# Power_Supply.net
KiCad netlist of a schematic drawn in Altium Designer
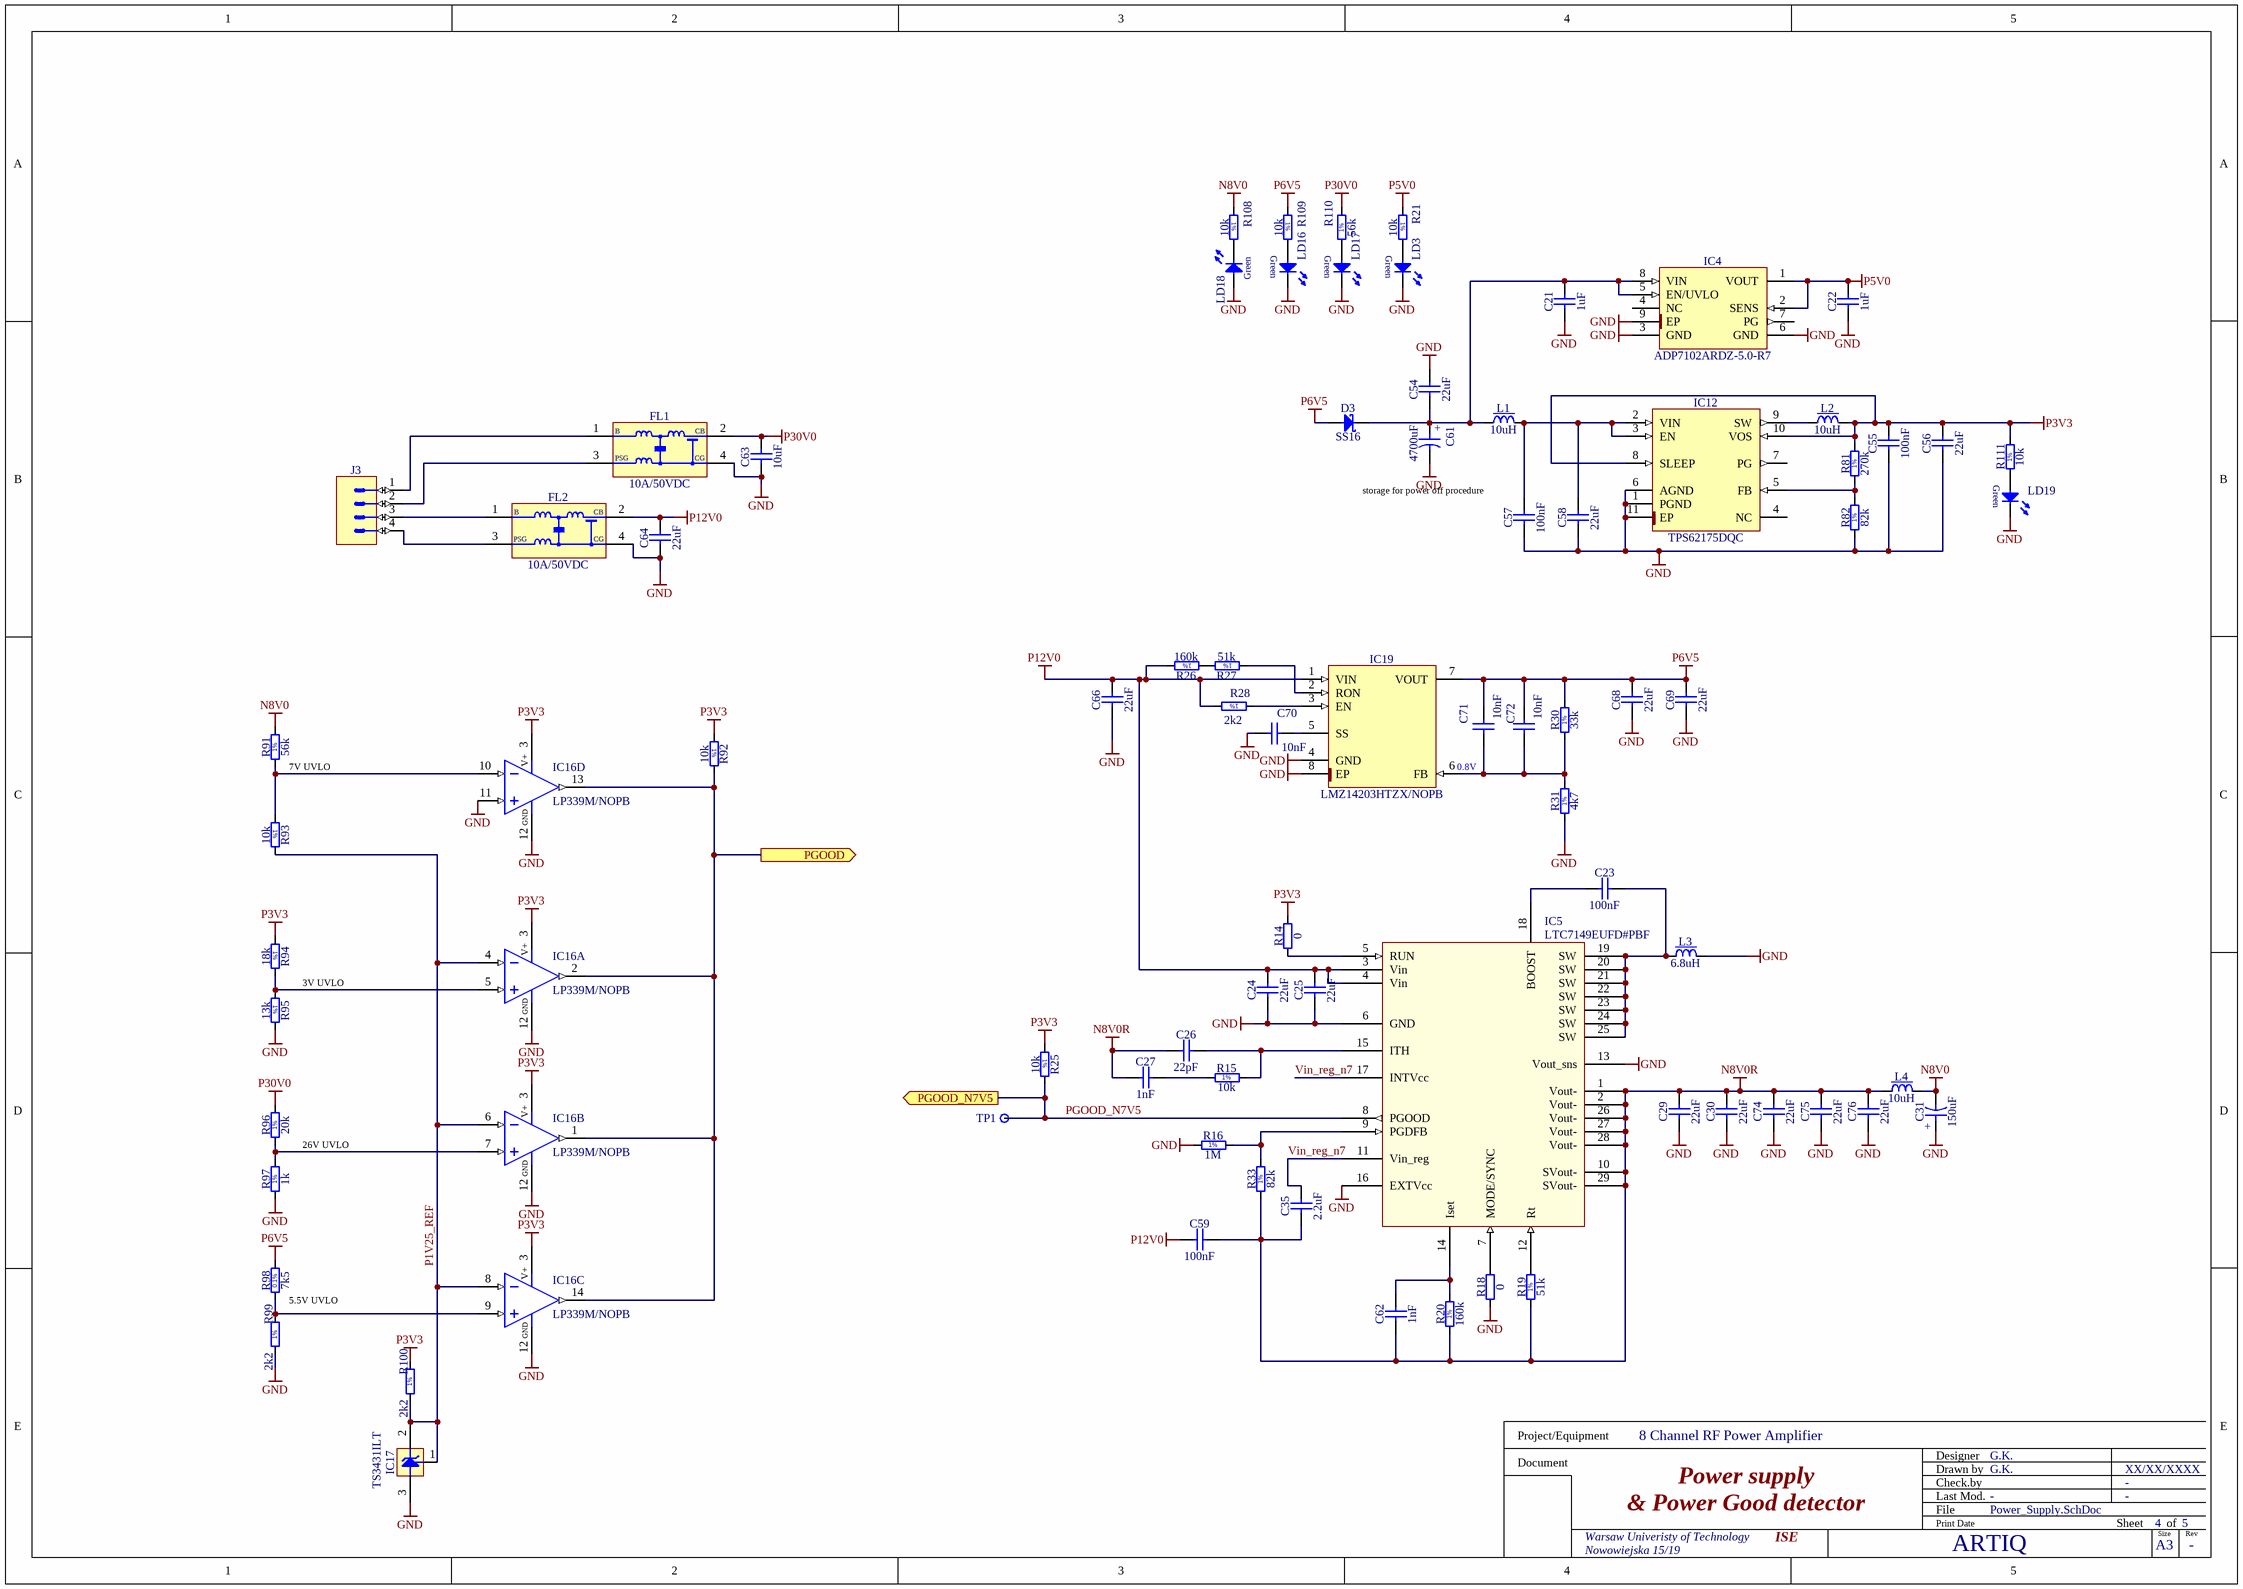
[diagram p0: Power_Supply.SchDoc]

(export (version "E")
  (design (tool "Eeschema 10.0.6"))
  (components
    (comp (ref "C21")
      (value "1uF")
      (footprint "CAPC2012X140N")
      (description "Non-polarised capacitor")
      (fields
        (field (name "PART NUMBER") "CC0805_1UF_35V_20%_X7R")
        (field (name "VOLTAGE") "35V")
        (field (name "AUTHOR") "CERN DEM JLC")
      )
      (libsource (lib "Capacitors") (part "Capacitor - non polarized"))
    )
    (comp (ref "C22")
      (value "1uF")
      (footprint "CAPC2012X140N")
      (description "Non-polarised capacitor")
      (fields
        (field (name "PART NUMBER") "CC0805_1UF_35V_20%_X7R")
        (field (name "VOLTAGE") "35V")
        (field (name "AUTHOR") "CERN DEM JLC")
      )
      (libsource (lib "Capacitors") (part "Capacitor - non polarized"))
    )
    (comp (ref "C23")
      (value "100nF")
      (footprint "CAPC1005X55N")
      (description "Non-polarised capacitor")
      (fields
        (field (name "PART NUMBER") "CC0402_100NF_16V_10%_X7R")
        (field (name "VOLTAGE") "16V")
        (field (name "AUTHOR") "CERN DEM JLC")
      )
      (libsource (lib "Capacitors") (part "Capacitor - non polarized"))
    )
    (comp (ref "C24")
      (value "22uF")
      (footprint "CAPC2012X135N")
      (description "Non-polarised capacitor")
      (fields
        (field (name "PART NUMBER") "CC0805_22UF_16V_10%_X5R")
        (field (name "VOLTAGE") "16V")
        (field (name "AUTHOR") "CERN DEM JLC")
      )
      (libsource (lib "Capacitors") (part "Capacitor - non polarized"))
    )
    (comp (ref "C25")
      (value "22uF")
      (footprint "CAPC2012X135N")
      (description "Non-polarised capacitor")
      (fields
        (field (name "PART NUMBER") "CC0805_22UF_16V_10%_X5R")
        (field (name "VOLTAGE") "16V")
        (field (name "AUTHOR") "CERN DEM JLC")
      )
      (libsource (lib "Capacitors") (part "Capacitor - non polarized"))
    )
    (comp (ref "C26")
      (value "22pF")
      (footprint "CAPC1005X55N")
      (description "Non-polarised capacitor")
      (fields
        (field (name "PART NUMBER") "CC0402_22PF_50V_5%_C0G")
        (field (name "VOLTAGE") "50V")
        (field (name "AUTHOR") "CERN DEM JLC")
      )
      (libsource (lib "Capacitors") (part "Capacitor - non polarized"))
    )
    (comp (ref "C27")
      (value "1nF")
      (footprint "CAPC1005X55N")
      (description "Non-polarised capacitor")
      (fields
        (field (name "PART NUMBER") "CC0402_1NF_50V_10%_X7R")
        (field (name "VOLTAGE") "50V")
        (field (name "AUTHOR") "CERN DEM JLC")
      )
      (libsource (lib "Capacitors") (part "Capacitor - non polarized"))
    )
    (comp (ref "C29")
      (value "22uF")
      (footprint "CAPC2012X135N")
      (description "Non-polarised capacitor")
      (fields
        (field (name "PART NUMBER") "CC0805_22UF_16V_10%_X5R")
        (field (name "VOLTAGE") "16V")
        (field (name "AUTHOR") "CERN DEM JLC")
      )
      (libsource (lib "Capacitors") (part "Capacitor - non polarized"))
    )
    (comp (ref "C30")
      (value "22uF")
      (footprint "CAPC2012X135N")
      (description "Non-polarised capacitor")
      (fields
        (field (name "PART NUMBER") "CC0805_22UF_16V_10%_X5R")
        (field (name "VOLTAGE") "16V")
        (field (name "AUTHOR") "CERN DEM JLC")
      )
      (libsource (lib "Capacitors") (part "Capacitor - non polarized"))
    )
    (comp (ref "C31")
      (value "150uF")
      (footprint "CAPMP7343X310N")
      (description "Polarised capacitor")
      (fields
        (field (name "PART NUMBER") "CTE7343-31_150UF_16V_10%_LESR0100")
        (field (name "VOLTAGE") "16V")
        (field (name "AUTHOR") "CERN DEM JLC")
      )
      (libsource (lib "Capacitors") (part "Capacitor - polarized"))
    )
    (comp (ref "C35")
      (value "2.2uF")
      (footprint "CAPC1608X87N")
      (description "Non-polarised capacitor")
      (fields
        (field (name "PART NUMBER") "CC0603_2.2UF_16V_10%_X5R")
        (field (name "VOLTAGE") "16V")
        (field (name "AUTHOR") "CERN DEM JLC")
      )
      (libsource (lib "Capacitors") (part "Capacitor - non polarized"))
    )
    (comp (ref "C54")
      (value "22uF")
      (footprint "CAPC2012X135N")
      (description "Non-polarised capacitor")
      (fields
        (field (name "PART NUMBER") "CC0805_22UF_16V_10%_X5R")
        (field (name "VOLTAGE") "16V")
        (field (name "AUTHOR") "CERN DEM JLC")
      )
      (libsource (lib "Capacitors") (part "Capacitor - non polarized"))
    )
    (comp (ref "C55")
      (value "100nF")
      (footprint "CAPC1005X55N")
      (description "Non-polarised capacitor")
      (fields
        (field (name "PART NUMBER") "CC0402_100NF_16V_10%_X5R")
        (field (name "VOLTAGE") "16V")
        (field (name "AUTHOR") "CERN DEM JLC")
      )
      (libsource (lib "Capacitors") (part "Capacitor - non polarized"))
    )
    (comp (ref "C56")
      (value "22uF")
      (footprint "CAPC2012X135N")
      (description "Non-polarised capacitor")
      (fields
        (field (name "PART NUMBER") "CC0805_22UF_16V_10%_X5R")
        (field (name "VOLTAGE") "16V")
        (field (name "AUTHOR") "CERN DEM JLC")
      )
      (libsource (lib "Capacitors") (part "Capacitor - non polarized"))
    )
    (comp (ref "C57")
      (value "100nF")
      (footprint "CAPC1005X55N")
      (description "Non-polarised capacitor")
      (fields
        (field (name "PART NUMBER") "CC0402_100NF_16V_10%_X5R")
        (field (name "VOLTAGE") "16V")
        (field (name "AUTHOR") "CERN DEM JLC")
      )
      (libsource (lib "Capacitors") (part "Capacitor - non polarized"))
    )
    (comp (ref "C58")
      (value "22uF")
      (footprint "CAPC2012X135N")
      (description "Non-polarised capacitor")
      (fields
        (field (name "PART NUMBER") "CC0805_22UF_16V_10%_X5R")
        (field (name "VOLTAGE") "16V")
        (field (name "AUTHOR") "CERN DEM JLC")
      )
      (libsource (lib "Capacitors") (part "Capacitor - non polarized"))
    )
    (comp (ref "C59")
      (value "100nF")
      (footprint "CAPC1608X87N")
      (description "Non-polarised capacitor")
      (fields
        (field (name "PART NUMBER") "CC0603_100NF_50V_10%_X5R")
        (field (name "VOLTAGE") "50V")
        (field (name "AUTHOR") "CERN DEM MR")
      )
      (libsource (lib "Capacitors") (part "Capacitor - non polarized"))
    )
    (comp (ref "C61")
      (value "4700uF")
      (footprint "CAPAE1900X1680N")
      (description "Polarised capacitor")
      (fields
        (field (name "PART NUMBER") "CAE1900-1680_4700UF_16V_20%")
        (field (name "VOLTAGE") "16V")
        (field (name "AUTHOR") "CERN DEM JLC")
      )
      (libsource (lib "Capacitors") (part "Capacitor - polarized"))
    )
    (comp (ref "C62")
      (value "1nF")
      (footprint "CAPC1005X55N")
      (description "Non-polarised capacitor")
      (fields
        (field (name "PART NUMBER") "CC0402_1NF_50V_10%_X7R")
        (field (name "VOLTAGE") "50V")
        (field (name "AUTHOR") "CERN DEM JLC")
      )
      (libsource (lib "Capacitors") (part "Capacitor - non polarized"))
    )
    (comp (ref "C63")
      (value "10uF")
      (footprint "CAPC3216X190N")
      (description "Non-polarised capacitor")
      (fields
        (field (name "PART NUMBER") "CC1206_10UF_50V_10%_X5R_TDK_CGA5L3X5R1H106K160AB")
        (field (name "VOLTAGE") "50V")
        (field (name "AUTHOR") "CERN DEM BC")
      )
      (libsource (lib "Capacitors") (part "Capacitor - non polarized"))
    )
    (comp (ref "C64")
      (value "22uF")
      (footprint "CAPC2012X135N")
      (description "Non-polarised capacitor")
      (fields
        (field (name "PART NUMBER") "CC0805_22UF_16V_10%_X5R")
        (field (name "VOLTAGE") "16V")
        (field (name "AUTHOR") "CERN DEM JLC")
      )
      (libsource (lib "Capacitors") (part "Capacitor - non polarized"))
    )
    (comp (ref "C66")
      (value "22uF")
      (footprint "CAPC2012X135N")
      (description "Non-polarised capacitor")
      (fields
        (field (name "PART NUMBER") "CC0805_22UF_16V_10%_X5R")
        (field (name "VOLTAGE") "16V")
        (field (name "AUTHOR") "CERN DEM JLC")
      )
      (libsource (lib "Capacitors") (part "Capacitor - non polarized"))
    )
    (comp (ref "C68")
      (value "22uF")
      (footprint "CAPC2012X135N")
      (description "Non-polarised capacitor")
      (fields
        (field (name "PART NUMBER") "CC0805_22UF_16V_10%_X5R")
        (field (name "VOLTAGE") "16V")
        (field (name "AUTHOR") "CERN DEM JLC")
      )
      (libsource (lib "Capacitors") (part "Capacitor - non polarized"))
    )
    (comp (ref "C69")
      (value "22uF")
      (footprint "CAPC2012X135N")
      (description "Non-polarised capacitor")
      (fields
        (field (name "PART NUMBER") "CC0805_22UF_16V_10%_X5R")
        (field (name "VOLTAGE") "16V")
        (field (name "AUTHOR") "CERN DEM JLC")
      )
      (libsource (lib "Capacitors") (part "Capacitor - non polarized"))
    )
    (comp (ref "C70")
      (value "10nF")
      (footprint "CAPC1608X87N")
      (description "Non-polarised capacitor")
      (fields
        (field (name "PART NUMBER") "CC0603_10NF_50V_5%_C0G")
        (field (name "VOLTAGE") "50V")
        (field (name "AUTHOR") "CERN DEM JLC")
      )
      (libsource (lib "Capacitors") (part "Capacitor - non polarized"))
    )
    (comp (ref "C71")
      (value "10nF")
      (footprint "CAPC1608X87N")
      (description "Non-polarised capacitor")
      (fields
        (field (name "PART NUMBER") "CC0603_10NF_50V_5%_C0G")
        (field (name "VOLTAGE") "50V")
        (field (name "AUTHOR") "CERN DEM JLC")
      )
      (libsource (lib "Capacitors") (part "Capacitor - non polarized"))
    )
    (comp (ref "C72")
      (value "10nF")
      (footprint "CAPC1608X87N")
      (description "Non-polarised capacitor")
      (fields
        (field (name "PART NUMBER") "CC0603_10NF_50V_5%_C0G")
        (field (name "VOLTAGE") "50V")
        (field (name "AUTHOR") "CERN DEM JLC")
      )
      (libsource (lib "Capacitors") (part "Capacitor - non polarized"))
    )
    (comp (ref "C74")
      (value "22uF")
      (footprint "CAPC2012X135N")
      (description "Non-polarised capacitor")
      (fields
        (field (name "PART NUMBER") "CC0805_22UF_16V_10%_X5R")
        (field (name "VOLTAGE") "16V")
        (field (name "AUTHOR") "CERN DEM JLC")
      )
      (libsource (lib "Capacitors") (part "Capacitor - non polarized"))
    )
    (comp (ref "C75")
      (value "22uF")
      (footprint "CAPC2012X135N")
      (description "Non-polarised capacitor")
      (fields
        (field (name "PART NUMBER") "CC0805_22UF_16V_10%_X5R")
        (field (name "VOLTAGE") "16V")
        (field (name "AUTHOR") "CERN DEM JLC")
      )
      (libsource (lib "Capacitors") (part "Capacitor - non polarized"))
    )
    (comp (ref "C76")
      (value "22uF")
      (footprint "CAPC2012X135N")
      (description "Non-polarised capacitor")
      (fields
        (field (name "PART NUMBER") "CC0805_22UF_16V_10%_X5R")
        (field (name "VOLTAGE") "16V")
        (field (name "AUTHOR") "CERN DEM JLC")
      )
      (libsource (lib "Capacitors") (part "Capacitor - non polarized"))
    )
    (comp (ref "D3")
      (value "SS16")
      (footprint "DIOM5127X229N")
      (description "Schottky Diode")
      (fields
        (field (name "VOLTAGE") "60V")
        (field (name "POWER") "1A")
        (field (name "AUTHOR") "CERN DEM JLC")
      )
      (libsource (lib "ICs And Semiconductors") (part "Diode Schottky"))
    )
    (comp (ref "FL1")
      (value "10A/50VDC")
      (footprint "FIL_MURATA_BNX02")
      (description "Block Type EMIFIL (LC Combined)")
      (fields
        (field (name "PART NUMBER") "FIL_MURATA_BNX022-01L")
        (field (name "MANUFACTURER") "MURATA")
        (field (name "AUTHOR") "CERN DEM JLC")
      )
      (libsource (lib "Inductors & Transformers") (part "FIL_MURATA_BNX02"))
    )
    (comp (ref "FL2")
      (value "10A/50VDC")
      (footprint "FIL_MURATA_BNX02")
      (description "Block Type EMIFIL (LC Combined)")
      (fields
        (field (name "PART NUMBER") "FIL_MURATA_BNX022-01L")
        (field (name "MANUFACTURER") "MURATA")
        (field (name "AUTHOR") "CERN DEM JLC")
      )
      (libsource (lib "Inductors & Transformers") (part "FIL_MURATA_BNX02"))
    )
    (comp (ref "IC4")
      (value "ADP7102ARDZ-5.0-R7")
      (footprint "SOIC127P600X175-9N-R241X309")
      (description "300 mA, Low Noise, CMOS LDO Linear Regulator")
      (fields (field (name "MANUFACTURER") "ANALOG DEVICES") (field (name "AUTHOR") "CERN DEM JLC"))
      (libsource (lib "ICs And Semiconductors") (part "ADP7102ARDZ-X.X-R7"))
    )
    (comp (ref "IC5")
      (value "LTC7149EUFD#PBF")
      (footprint "QFN50P400X500X80_HS-29N")
      (description "LTC7149 - 60V, 4A Synchronous Step-Down Regulator for Inverting Outputs")
      (fields (field (name "MANUFACTURER") "Linear technology"))
      (libsource (lib "misc") (part "LTC7149EUFD#PBF"))
    )
    (comp (ref "IC12")
      (value "TPS62175DQC")
      (footprint "SON50P200X300X80-11N-R94X250")
      (description "4.75-28VDC to 1-6VDC, 500mA Step-Down Converter With Sleep Mode")
      (fields (field (name "MANUFACTURER") "TEXAS INSTRUMENTS") (field (name "AUTHOR") "CERN DEM JMW"))
      (libsource (lib "ICs And Semiconductors") (part "TPS62175"))
    )
    (comp (ref "IC16")
      (value "LP339M/NOPB")
      (footprint "SOIC127P600X175-14N")
      (description "Quad Operational Amplifier")
      (fields (field (name "MANUFACTURER") "TEXAS INSTRUMENTS") (field (name "AUTHOR") "CERN DEM MR"))
      (libsource (lib "ICs And Semiconductors") (part "Operational Amplifier x4 Type5"))
    )
    (comp (ref "IC17")
      (value "TS3431ILT")
      (footprint "SOT95P237X112-3N")
      (description "Precision Reference 1=Adj 2=Cathode 3=Anode")
      (fields (field (name "MANUFACTURER") "ST MICROELECTRONICS") (field (name "AUTHOR") "CERN DEM JLC"))
      (libsource (lib "ICs And Semiconductors") (part "VREF 1ADJ-2C-3A"))
    )
    (comp (ref "IC19")
      (value "LMZ14203HTZX/NOPB")
      (footprint "TEXAS_TO-PMOD (NDW)")
      (description "3A SIMPLE SWITCHER® Power Module with 42V Maximum Input Voltage")
      (fields (field (name "MANUFACTURER") "TEXAS INSTRUMENTS") (field (name "AUTHOR") "GK"))
      (libsource (lib "LIBRARY_SCH") (part "PM_LMZ14203"))
    )
    (comp (ref "J3")
      (value "~")
      (footprint "PHOENIX_1755752")
      (description "Connector 4 Male")
      (fields
        (field (name "PART NUMBER") "PHOENIX_1755752")
        (field (name "MANUFACTURER") "PHOENIX CONTACT")
        (field (name "AUTHOR") "CERN DEM JLC")
      )
      (libsource (lib "Connectors") (part "Connector 4 Male"))
    )
    (comp (ref "L1")
      (value "10uH")
      (footprint "IND_MURATA-PS_8400")
      (description "Inductor With Core")
      (fields
        (field (name "PART NUMBER") "IND_10UH_10%_MURATA-PS_8400")
        (field (name "POWER") "950mA")
        (field (name "AUTHOR") "CERN DEM JLC")
      )
      (libsource (lib "Inductors & Transformers") (part "Inductor With Magnetic core"))
    )
    (comp (ref "L2")
      (value "10uH")
      (footprint "IND_MURATA-PS_8400")
      (description "Inductor With Core")
      (fields
        (field (name "PART NUMBER") "IND_10UH_10%_MURATA-PS_8400")
        (field (name "POWER") "950mA")
        (field (name "AUTHOR") "CERN DEM JLC")
      )
      (libsource (lib "Inductors & Transformers") (part "Inductor With Magnetic core"))
    )
    (comp (ref "L3")
      (value "6.8uH")
      (footprint "INDM6965X300N")
      (description "Inductor With Core")
      (fields
        (field (name "PART NUMBER") "IND2525_1.5UH_20%_VISHAY_IHLP-2525CZ")
        (field (name "POWER") "9A")
        (field (name "AUTHOR") "CERN DEM JLC")
      )
      (libsource (lib "Inductors & Transformers") (part "Inductor With Magnetic core"))
    )
    (comp (ref "L4")
      (value "10uH")
      (footprint "IND_MURATA-PS_8400")
      (description "Inductor With Core")
      (fields
        (field (name "PART NUMBER") "IND_10UH_10%_MURATA-PS_8400")
        (field (name "POWER") "950mA")
        (field (name "AUTHOR") "CERN DEM JLC")
      )
      (libsource (lib "Inductors & Transformers") (part "Inductor With Magnetic core"))
    )
    (comp (ref "LD3")
      (value "Green")
      (footprint "LED_KINGBRIGHT_KPH-1608CGCK")
      (description "LED Green 1C 2A")
      (fields
        (field (name "PART NUMBER") "LED_KINGBRIGHT_KPH-1608CGCK")
        (field (name "MANUFACTURER") "KINGBRIGHT")
        (field (name "AUTHOR") "CERN DEM JLC")
      )
      (libsource (lib "ICs And Semiconductors") (part "LED Green 1C 2A"))
    )
    (comp (ref "LD16")
      (value "Green")
      (footprint "LED_KINGBRIGHT_KPH-1608CGCK")
      (description "LED Green 1C 2A")
      (fields
        (field (name "PART NUMBER") "LED_KINGBRIGHT_KPH-1608CGCK")
        (field (name "MANUFACTURER") "KINGBRIGHT")
        (field (name "AUTHOR") "CERN DEM JLC")
      )
      (libsource (lib "ICs And Semiconductors") (part "LED Green 1C 2A"))
    )
    (comp (ref "LD17")
      (value "Green")
      (footprint "LED_KINGBRIGHT_KPH-1608CGCK")
      (description "LED Green 1C 2A")
      (fields
        (field (name "PART NUMBER") "LED_KINGBRIGHT_KPH-1608CGCK")
        (field (name "MANUFACTURER") "KINGBRIGHT")
        (field (name "AUTHOR") "CERN DEM JLC")
      )
      (libsource (lib "ICs And Semiconductors") (part "LED Green 1C 2A"))
    )
    (comp (ref "LD18")
      (value "Green")
      (footprint "LED_KINGBRIGHT_KPH-1608CGCK")
      (description "LED Green 1C 2A")
      (fields
        (field (name "PART NUMBER") "LED_KINGBRIGHT_KPH-1608CGCK")
        (field (name "MANUFACTURER") "KINGBRIGHT")
        (field (name "AUTHOR") "CERN DEM JLC")
      )
      (libsource (lib "ICs And Semiconductors") (part "LED Green 1C 2A"))
    )
    (comp (ref "LD19")
      (value "Green")
      (footprint "LED_OSRAM_LGL29K")
      (description "LED Green 1C 2A")
      (fields
        (field (name "PART NUMBER") "LED_OSRAM_LG L29K-G2J1-24-Z")
        (field (name "MANUFACTURER") "OSRAM")
        (field (name "AUTHOR") "CERN DEM JLC")
      )
      (libsource (lib "ICs And Semiconductors") (part "LED Green 1C 2A"))
    )
    (comp (ref "R14")
      (value "0")
      (footprint "RESC1005X40N")
      (description "Resistor")
      (fields
        (field (name "PART NUMBER") "R0402_0R_JUMPER")
        (field (name "MANUFACTURER") "GENERIC")
        (field (name "AUTHOR") "CERN DEM JLC")
      )
      (libsource (lib "Resistors") (part "Resistor"))
    )
    (comp (ref "R15")
      (value "10k")
      (footprint "RESC1005X40N")
      (description "Resistor - 1%")
      (fields
        (field (name "PART NUMBER") "R0402_10K_1%_0.0625W_100PPM")
        (field (name "POWER") "0.0625W")
        (field (name "AUTHOR") "CERN DEM JLC")
      )
      (libsource (lib "Resistors") (part "Resistor - 1%"))
    )
    (comp (ref "R16")
      (value "1M")
      (footprint "RESC1005X40N")
      (description "Resistor - 1%")
      (fields
        (field (name "PART NUMBER") "R0402_1M_1%_0.0625W_100PPM")
        (field (name "POWER") "0.0625W")
        (field (name "AUTHOR") "CERN DEM JLC")
      )
      (libsource (lib "Resistors") (part "Resistor - 1%"))
    )
    (comp (ref "R18")
      (value "0")
      (footprint "RESC1005X40N")
      (description "Resistor")
      (fields
        (field (name "PART NUMBER") "R0402_0R_JUMPER")
        (field (name "MANUFACTURER") "GENERIC")
        (field (name "AUTHOR") "CERN DEM JLC")
      )
      (libsource (lib "Resistors") (part "Resistor"))
    )
    (comp (ref "R19")
      (value "51k")
      (footprint "RESC1005X40N")
      (description "Resistor - 1%")
      (fields
        (field (name "PART NUMBER") "R0402_51K_1%_0.0625W_100PPM")
        (field (name "POWER") "0.0625W")
        (field (name "AUTHOR") "CERN DEM JLC")
      )
      (libsource (lib "Resistors") (part "Resistor - 1%"))
    )
    (comp (ref "R20")
      (value "160k")
      (footprint "RESC1005X40N")
      (description "Resistor - 1%")
      (fields
        (field (name "PART NUMBER") "R0402_160K_1%_0.0625W_100PPM")
        (field (name "POWER") "0.0625W")
        (field (name "AUTHOR") "CERN DEM JLC")
      )
      (libsource (lib "Resistors") (part "Resistor - 1%"))
    )
    (comp (ref "R21")
      (value "10k")
      (footprint "RESC1005X40N")
      (description "Resistor - 1%")
      (fields
        (field (name "PART NUMBER") "R0402_10K_1%_0.0625W_100PPM")
        (field (name "POWER") "0.0625W")
        (field (name "AUTHOR") "CERN DEM JLC")
      )
      (libsource (lib "Resistors") (part "Resistor - 1%"))
    )
    (comp (ref "R25")
      (value "10k")
      (footprint "RESC1005X40N")
      (description "Resistor - 1%")
      (fields
        (field (name "PART NUMBER") "R0402_10K_1%_0.0625W_100PPM")
        (field (name "POWER") "0.0625W")
        (field (name "AUTHOR") "CERN DEM JLC")
      )
      (libsource (lib "Resistors") (part "Resistor - 1%"))
    )
    (comp (ref "R26")
      (value "160k")
      (footprint "RESC1005X40N")
      (description "Resistor - 1%")
      (fields
        (field (name "PART NUMBER") "R0402_160K_1%_0.0625W_100PPM")
        (field (name "POWER") "0.0625W")
        (field (name "AUTHOR") "CERN DEM JLC")
      )
      (libsource (lib "Resistors") (part "Resistor - 1%"))
    )
    (comp (ref "R27")
      (value "51k")
      (footprint "RESC1005X40N")
      (description "Resistor - 1%")
      (fields
        (field (name "PART NUMBER") "R0402_51K_1%_0.0625W_100PPM")
        (field (name "POWER") "0.0625W")
        (field (name "AUTHOR") "CERN DEM JLC")
      )
      (libsource (lib "Resistors") (part "Resistor - 1%"))
    )
    (comp (ref "R28")
      (value "2k2")
      (footprint "RESC1005X40N")
      (description "Resistor - 1%")
      (fields
        (field (name "PART NUMBER") "R0402_2K2_1%_0.0625W_100PPM")
        (field (name "POWER") "0.0625W")
        (field (name "AUTHOR") "CERN DEM JLC")
      )
      (libsource (lib "Resistors") (part "Resistor - 1%"))
    )
    (comp (ref "R30")
      (value "33k")
      (footprint "RESC1608X55N")
      (description "Resistor - 1%")
      (fields
        (field (name "PART NUMBER") "R0603_33K_1%_0.1W_100PPM")
        (field (name "POWER") "0.1W")
        (field (name "AUTHOR") "CERN DEM JLC")
      )
      (libsource (lib "Resistors") (part "Resistor - 1%"))
    )
    (comp (ref "R31")
      (value "4k7")
      (footprint "RESC1608X55N")
      (description "Resistor - 1%")
      (fields
        (field (name "PART NUMBER") "R0603_4K7_1%_0.1W_100PPM")
        (field (name "POWER") "0.1W")
        (field (name "AUTHOR") "CERN DEM JLC")
      )
      (libsource (lib "Resistors") (part "Resistor - 1%"))
    )
    (comp (ref "R33")
      (value "82k")
      (footprint "RESC1608X55N")
      (description "Resistor - 1%")
      (fields
        (field (name "PART NUMBER") "R0603_82K_1%_0.1W_100PPM")
        (field (name "POWER") "0.1W")
        (field (name "AUTHOR") "CERN DEM JLC")
      )
      (libsource (lib "Resistors") (part "Resistor - 1%"))
    )
    (comp (ref "R81")
      (value "270k")
      (footprint "RESC1608X55N")
      (description "Resistor - 1%")
      (fields
        (field (name "PART NUMBER") "R0603_270K_1%_0.1W_100PPM")
        (field (name "POWER") "0.1W")
        (field (name "AUTHOR") "CERN DEM JLC")
      )
      (libsource (lib "Resistors") (part "Resistor - 1%"))
    )
    (comp (ref "R82")
      (value "82k")
      (footprint "RESC1608X55N")
      (description "Resistor - 1%")
      (fields
        (field (name "PART NUMBER") "R0603_82K_1%_0.1W_100PPM")
        (field (name "POWER") "0.1W")
        (field (name "AUTHOR") "CERN DEM JLC")
      )
      (libsource (lib "Resistors") (part "Resistor - 1%"))
    )
    (comp (ref "R91")
      (value "56k")
      (footprint "RESC1608X55N")
      (description "Resistor - 1%")
      (fields
        (field (name "PART NUMBER") "R0603_56K_1%_0.1W_100PPM")
        (field (name "POWER") "0.1W")
        (field (name "AUTHOR") "CERN DEM JLC")
      )
      (libsource (lib "Resistors") (part "Resistor - 1%"))
    )
    (comp (ref "R92")
      (value "10k")
      (footprint "RESC1005X40N")
      (description "Resistor - 1%")
      (fields
        (field (name "PART NUMBER") "R0402_10K_1%_0.0625W_100PPM")
        (field (name "POWER") "0.0625W")
        (field (name "AUTHOR") "CERN DEM JLC")
      )
      (libsource (lib "Resistors") (part "Resistor - 1%"))
    )
    (comp (ref "R93")
      (value "10k")
      (footprint "RESC1005X40N")
      (description "Resistor - 1%")
      (fields
        (field (name "PART NUMBER") "R0402_10K_1%_0.0625W_100PPM")
        (field (name "POWER") "0.0625W")
        (field (name "AUTHOR") "CERN DEM JLC")
      )
      (libsource (lib "Resistors") (part "Resistor - 1%"))
    )
    (comp (ref "R94")
      (value "18k")
      (footprint "RESC1608X55N")
      (description "Resistor - 1%")
      (fields
        (field (name "PART NUMBER") "R0603_18K_1%_0.1W_100PPM")
        (field (name "POWER") "0.1W")
        (field (name "AUTHOR") "CERN DEM JLC")
      )
      (libsource (lib "Resistors") (part "Resistor - 1%"))
    )
    (comp (ref "R95")
      (value "13k")
      (footprint "RESC1608X55N")
      (description "Resistor - 1%")
      (fields
        (field (name "PART NUMBER") "R0603_13K_1%_0.1W_100PPM")
        (field (name "POWER") "0.1W")
        (field (name "AUTHOR") "CERN DEM JLC")
      )
      (libsource (lib "Resistors") (part "Resistor - 1%"))
    )
    (comp (ref "R96")
      (value "20k")
      (footprint "RESC1608X55N")
      (description "Resistor - 1%")
      (fields
        (field (name "PART NUMBER") "R0603_20K_1%_0.1W_100PPM")
        (field (name "POWER") "0.1W")
        (field (name "AUTHOR") "CERN DEM JLC")
      )
      (libsource (lib "Resistors") (part "Resistor - 1%"))
    )
    (comp (ref "R97")
      (value "1k")
      (footprint "RESC1608X55N")
      (description "Resistor - 1%")
      (fields
        (field (name "PART NUMBER") "R0603_1K_1%_0.1W_100PPM")
        (field (name "POWER") "0.1W")
        (field (name "AUTHOR") "CERN DEM JLC")
      )
      (libsource (lib "Resistors") (part "Resistor - 1%"))
    )
    (comp (ref "R98")
      (value "7k5")
      (footprint "RESC1608X55N")
      (description "Resistor - 0.1%")
      (fields
        (field (name "PART NUMBER") "R0603_7K5_0.1%_0.063W_10PPM")
        (field (name "POWER") "0.063W")
        (field (name "AUTHOR") "CERN DEM JLC")
      )
      (libsource (lib "Resistors") (part "Resistor - 0.1%"))
    )
    (comp (ref "R99")
      (value "2k2")
      (footprint "RESC1005X40N")
      (description "Resistor - 1%")
      (fields
        (field (name "PART NUMBER") "R0402_2K2_1%_0.0625W_100PPM")
        (field (name "POWER") "0.0625W")
        (field (name "AUTHOR") "CERN DEM JLC")
      )
      (libsource (lib "Resistors") (part "Resistor - 1%"))
    )
    (comp (ref "R100")
      (value "2k2")
      (footprint "RESC1005X40N")
      (description "Resistor - 1%")
      (fields
        (field (name "PART NUMBER") "R0402_2K2_1%_0.0625W_100PPM")
        (field (name "POWER") "0.0625W")
        (field (name "AUTHOR") "CERN DEM JLC")
      )
      (libsource (lib "Resistors") (part "Resistor - 1%"))
    )
    (comp (ref "R108")
      (value "10k")
      (footprint "RESC1005X40N")
      (description "Resistor - 1%")
      (fields
        (field (name "PART NUMBER") "R0402_10K_1%_0.0625W_100PPM")
        (field (name "POWER") "0.0625W")
        (field (name "AUTHOR") "CERN DEM JLC")
      )
      (libsource (lib "Resistors") (part "Resistor - 1%"))
    )
    (comp (ref "R109")
      (value "10k")
      (footprint "RESC1005X40N")
      (description "Resistor - 1%")
      (fields
        (field (name "PART NUMBER") "R0402_10K_1%_0.0625W_100PPM")
        (field (name "POWER") "0.0625W")
        (field (name "AUTHOR") "CERN DEM JLC")
      )
      (libsource (lib "Resistors") (part "Resistor - 1%"))
    )
    (comp (ref "R110")
      (value "56k")
      (footprint "RESC1608X55N")
      (description "Resistor - 1%")
      (fields
        (field (name "PART NUMBER") "R0603_56K_1%_0.1W_100PPM")
        (field (name "POWER") "0.1W")
        (field (name "AUTHOR") "CERN DEM JLC")
      )
      (libsource (lib "Resistors") (part "Resistor - 1%"))
    )
    (comp (ref "R111")
      (value "10k")
      (footprint "RESC1005X40N")
      (description "Resistor - 1%")
      (fields
        (field (name "PART NUMBER") "R0402_10K_1%_0.0625W_100PPM")
        (field (name "POWER") "0.0625W")
        (field (name "AUTHOR") "CERN DEM JLC")
      )
      (libsource (lib "Resistors") (part "Resistor - 1%"))
    )
    (comp (ref "TP1")
      (value "Test Point")
      (footprint "TPS127")
      (fields (field (name "PART NUMBER") "SMD_PAD_1.27X1.27MM") (field (name "AUTHOR") "CERN DEM JLC"))
      (libsource (lib "Eletro-mechanical") (part "Test Point"))
    )
  )
  (nets
    (net (code "1") (name "/P1V25_REF") (class "Default")
      (node (ref "IC16") (pin "4") (pinfunction "IN-_4") (pintype "input"))
      (node (ref "IC16") (pin "6") (pinfunction "IN-_6") (pintype "input"))
      (node (ref "IC16") (pin "8") (pinfunction "IN-_8") (pintype "input"))
      (node (ref "IC17") (pin "1") (pinfunction "Adj_1") (pintype "passive"))
      (node (ref "IC17") (pin "2") (pinfunction "C_2") (pintype "passive"))
      (node (ref "R100") (pin "1") (pinfunction "1_1") (pintype "passive"))
      (node (ref "R93") (pin "2") (pinfunction "2_2") (pintype "passive"))
    )
    (net (code "2") (name "/PGOOD") (class "Default")
      (node (ref "IC16") (pin "1") (pinfunction "OUT_1") (pintype "output"))
      (node (ref "IC16") (pin "13") (pinfunction "OUT_13") (pintype "output"))
      (node (ref "IC16") (pin "14") (pinfunction "OUT_14") (pintype "output"))
      (node (ref "IC16") (pin "2") (pinfunction "OUT_2") (pintype "output"))
      (node (ref "R92") (pin "2") (pinfunction "2_2") (pintype "passive"))
    )
    (net (code "3") (name "/PGOOD_N7V5") (class "Default")
      (node (ref "IC5") (pin "8") (pinfunction "PGOOD_8") (pintype "output"))
      (node (ref "R25") (pin "2") (pinfunction "2_2") (pintype "passive"))
      (node (ref "TP1") (pin "1") (pinfunction "1_1") (pintype "bidirectional"))
    )
    (net (code "4") (name "/Vin_reg_n7") (class "Default")
      (node (ref "C35") (pin "2") (pinfunction "2_2") (pintype "passive"))
      (node (ref "IC5") (pin "11") (pinfunction "Vin_reg_11") (pintype "passive"))
      (node (ref "IC5") (pin "17") (pinfunction "INTVcc_17") (pintype "power_in"))
    )
    (net (code "5") (name "GND") (class "Default")
      (node (ref "C21") (pin "1") (pinfunction "1_1") (pintype "passive"))
      (node (ref "C22") (pin "1") (pinfunction "1_1") (pintype "passive"))
      (node (ref "C24") (pin "1") (pinfunction "1_1") (pintype "passive"))
      (node (ref "C25") (pin "1") (pinfunction "1_1") (pintype "passive"))
      (node (ref "C29") (pin "1") (pinfunction "1_1") (pintype "passive"))
      (node (ref "C30") (pin "1") (pinfunction "1_1") (pintype "passive"))
      (node (ref "C31") (pin "1") (pinfunction "1_1") (pintype "passive"))
      (node (ref "C54") (pin "2") (pinfunction "2_2") (pintype "passive"))
      (node (ref "C55") (pin "1") (pinfunction "1_1") (pintype "passive"))
      (node (ref "C56") (pin "1") (pinfunction "1_1") (pintype "passive"))
      (node (ref "C57") (pin "1") (pinfunction "1_1") (pintype "passive"))
      (node (ref "C58") (pin "1") (pinfunction "1_1") (pintype "passive"))
      (node (ref "C61") (pin "2") (pinfunction "2_2") (pintype "passive"))
      (node (ref "C63") (pin "1") (pinfunction "1_1") (pintype "passive"))
      (node (ref "C64") (pin "1") (pinfunction "1_1") (pintype "passive"))
      (node (ref "C66") (pin "1") (pinfunction "1_1") (pintype "passive"))
      (node (ref "C68") (pin "1") (pinfunction "1_1") (pintype "passive"))
      (node (ref "C69") (pin "1") (pinfunction "1_1") (pintype "passive"))
      (node (ref "C70") (pin "1") (pinfunction "1_1") (pintype "passive"))
      (node (ref "C74") (pin "1") (pinfunction "1_1") (pintype "passive"))
      (node (ref "C75") (pin "1") (pinfunction "1_1") (pintype "passive"))
      (node (ref "C76") (pin "1") (pinfunction "1_1") (pintype "passive"))
      (node (ref "FL1") (pin "4") (pinfunction "CG_4") (pintype "passive"))
      (node (ref "FL2") (pin "4") (pinfunction "CG_4") (pintype "passive"))
      (node (ref "IC12") (pin "1") (pinfunction "PGND_1") (pintype "power_in"))
      (node (ref "IC12") (pin "11") (pinfunction "EP_11") (pintype "power_in"))
      (node (ref "IC12") (pin "6") (pinfunction "AGND_6") (pintype "power_in"))
      (node (ref "IC16") (pin "11") (pinfunction "IN+_11") (pintype "input"))
      (node (ref "IC16") (pin "12") (pinfunction "GND_12") (pintype "power_in"))
      (node (ref "IC17") (pin "3") (pinfunction "A_3") (pintype "passive"))
      (node (ref "IC19") (pin "4") (pinfunction "GND_4") (pintype "power_in"))
      (node (ref "IC19") (pin "8") (pinfunction "EP_8") (pintype "power_in"))
      (node (ref "IC4") (pin "3") (pinfunction "GND_3") (pintype "power_in"))
      (node (ref "IC4") (pin "6") (pinfunction "GND_6") (pintype "power_in"))
      (node (ref "IC4") (pin "9") (pinfunction "EP_9") (pintype "power_in"))
      (node (ref "IC5") (pin "13") (pinfunction "Vout_sns_13") (pintype "passive"))
      (node (ref "IC5") (pin "16") (pinfunction "EXTVcc_16") (pintype "power_in"))
      (node (ref "IC5") (pin "6") (pinfunction "GND_6") (pintype "power_in"))
      (node (ref "L3") (pin "2") (pinfunction "2_2") (pintype "passive"))
      (node (ref "LD16") (pin "1") (pinfunction "C_1") (pintype "passive"))
      (node (ref "LD17") (pin "1") (pinfunction "C_1") (pintype "passive"))
      (node (ref "LD18") (pin "2") (pinfunction "A_2") (pintype "passive"))
      (node (ref "LD19") (pin "1") (pinfunction "C_1") (pintype "passive"))
      (node (ref "LD3") (pin "1") (pinfunction "C_1") (pintype "passive"))
      (node (ref "R16") (pin "1") (pinfunction "1_1") (pintype "passive"))
      (node (ref "R18") (pin "1") (pinfunction "1_1") (pintype "passive"))
      (node (ref "R31") (pin "1") (pinfunction "1_1") (pintype "passive"))
      (node (ref "R82") (pin "1") (pinfunction "1_1") (pintype "passive"))
      (node (ref "R95") (pin "2") (pinfunction "2_2") (pintype "passive"))
      (node (ref "R97") (pin "1") (pinfunction "1_1") (pintype "passive"))
      (node (ref "R99") (pin "1") (pinfunction "1_1") (pintype "passive"))
    )
    (net (code "6") (name "N8V0") (class "Default")
      (node (ref "C31") (pin "2") (pinfunction "2_2") (pintype "passive"))
      (node (ref "L4") (pin "2") (pinfunction "2_2") (pintype "passive"))
      (node (ref "R108") (pin "1") (pinfunction "1_1") (pintype "passive"))
      (node (ref "R91") (pin "2") (pinfunction "2_2") (pintype "passive"))
    )
    (net (code "7") (name "N8V0R") (class "Default")
      (node (ref "C26") (pin "1") (pinfunction "1_1") (pintype "passive"))
      (node (ref "C27") (pin "1") (pinfunction "1_1") (pintype "passive"))
      (node (ref "C29") (pin "2") (pinfunction "2_2") (pintype "passive"))
      (node (ref "C30") (pin "2") (pinfunction "2_2") (pintype "passive"))
      (node (ref "C35") (pin "1") (pinfunction "1_1") (pintype "passive"))
      (node (ref "C59") (pin "2") (pinfunction "2_2") (pintype "passive"))
      (node (ref "C62") (pin "1") (pinfunction "1_1") (pintype "passive"))
      (node (ref "C74") (pin "2") (pinfunction "2_2") (pintype "passive"))
      (node (ref "C75") (pin "2") (pinfunction "2_2") (pintype "passive"))
      (node (ref "C76") (pin "2") (pinfunction "2_2") (pintype "passive"))
      (node (ref "IC5") (pin "1") (pinfunction "Vout-_1") (pintype "power_in"))
      (node (ref "IC5") (pin "10") (pinfunction "SVout-_10") (pintype "power_in"))
      (node (ref "IC5") (pin "2") (pinfunction "Vout-_2") (pintype "power_in"))
      (node (ref "IC5") (pin "26") (pinfunction "Vout-_26") (pintype "power_in"))
      (node (ref "IC5") (pin "27") (pinfunction "Vout-_27") (pintype "power_in"))
      (node (ref "IC5") (pin "28") (pinfunction "Vout-_28") (pintype "power_in"))
      (node (ref "IC5") (pin "29") (pinfunction "SVout-_29") (pintype "power_in"))
      (node (ref "L4") (pin "1") (pinfunction "1_1") (pintype "passive"))
      (node (ref "R19") (pin "1") (pinfunction "1_1") (pintype "passive"))
      (node (ref "R20") (pin "1") (pinfunction "1_1") (pintype "passive"))
      (node (ref "R33") (pin "1") (pinfunction "1_1") (pintype "passive"))
    )
    (net (code "8") (name "Net-(C23-Pad2)") (class "Default")
      (node (ref "C23") (pin "2") (pinfunction "2_2") (pintype "passive"))
      (node (ref "IC5") (pin "19") (pinfunction "SW_19") (pintype "power_in"))
      (node (ref "IC5") (pin "20") (pinfunction "SW_20") (pintype "power_in"))
      (node (ref "IC5") (pin "21") (pinfunction "SW_21") (pintype "power_in"))
      (node (ref "IC5") (pin "22") (pinfunction "SW_22") (pintype "power_in"))
      (node (ref "IC5") (pin "23") (pinfunction "SW_23") (pintype "power_in"))
      (node (ref "IC5") (pin "24") (pinfunction "SW_24") (pintype "power_in"))
      (node (ref "IC5") (pin "25") (pinfunction "SW_25") (pintype "power_in"))
      (node (ref "L3") (pin "1") (pinfunction "1_1") (pintype "passive"))
    )
    (net (code "9") (name "Net-(C27-Pad2)") (class "Default")
      (node (ref "C27") (pin "2") (pinfunction "2_2") (pintype "passive"))
      (node (ref "R15") (pin "1") (pinfunction "1_1") (pintype "passive"))
    )
    (net (code "10") (name "Net-(D3-C)") (class "Default")
      (node (ref "C21") (pin "2") (pinfunction "2_2") (pintype "passive"))
      (node (ref "C54") (pin "1") (pinfunction "1_1") (pintype "passive"))
      (node (ref "C61") (pin "1") (pinfunction "1_1") (pintype "passive"))
      (node (ref "D3") (pin "1") (pinfunction "C_1") (pintype "passive"))
      (node (ref "IC4") (pin "5") (pinfunction "EN/UVLO_5") (pintype "input"))
      (node (ref "IC4") (pin "8") (pinfunction "VIN_8") (pintype "input"))
      (node (ref "L1") (pin "1") (pinfunction "1_1") (pintype "passive"))
    )
    (net (code "11") (name "Net-(FL1-B)") (class "Default")
      (node (ref "FL1") (pin "1") (pinfunction "B_1") (pintype "passive"))
      (node (ref "J3") (pin "1") (pinfunction "1_1") (pintype "bidirectional"))
    )
    (net (code "12") (name "Net-(FL1-PSG)") (class "Default")
      (node (ref "FL1") (pin "3") (pinfunction "PSG_3") (pintype "passive"))
      (node (ref "J3") (pin "2") (pinfunction "2_2") (pintype "bidirectional"))
    )
    (net (code "13") (name "Net-(FL2-B)") (class "Default")
      (node (ref "FL2") (pin "1") (pinfunction "B_1") (pintype "passive"))
      (node (ref "J3") (pin "3") (pinfunction "3_3") (pintype "bidirectional"))
    )
    (net (code "14") (name "Net-(FL2-PSG)") (class "Default")
      (node (ref "FL2") (pin "3") (pinfunction "PSG_3") (pintype "passive"))
      (node (ref "J3") (pin "4") (pinfunction "4_4") (pintype "bidirectional"))
    )
    (net (code "15") (name "Net-(IC5-BOOST)") (class "Default")
      (node (ref "C23") (pin "1") (pinfunction "1_1") (pintype "passive"))
      (node (ref "IC5") (pin "18") (pinfunction "BOOST_18") (pintype "passive"))
    )
    (net (code "16") (name "Net-(IC5-ITH)") (class "Default")
      (node (ref "C26") (pin "2") (pinfunction "2_2") (pintype "passive"))
      (node (ref "IC5") (pin "15") (pinfunction "ITH_15") (pintype "passive"))
      (node (ref "R15") (pin "2") (pinfunction "2_2") (pintype "passive"))
    )
    (net (code "17") (name "Net-(IC5-Iset)") (class "Default")
      (node (ref "C62") (pin "2") (pinfunction "2_2") (pintype "passive"))
      (node (ref "IC5") (pin "14") (pinfunction "Iset_14") (pintype "passive"))
      (node (ref "R20") (pin "2") (pinfunction "2_2") (pintype "passive"))
    )
    (net (code "18") (name "Net-(IC5-MODE{slash}SYNC)") (class "Default")
      (node (ref "IC5") (pin "7") (pinfunction "MODE/SYNC_7") (pintype "input"))
      (node (ref "R18") (pin "2") (pinfunction "2_2") (pintype "passive"))
    )
    (net (code "19") (name "Net-(IC5-PGDFB)") (class "Default")
      (node (ref "IC5") (pin "9") (pinfunction "PGDFB_9") (pintype "input"))
      (node (ref "R16") (pin "2") (pinfunction "2_2") (pintype "passive"))
      (node (ref "R33") (pin "2") (pinfunction "2_2") (pintype "passive"))
    )
    (net (code "20") (name "Net-(IC5-RUN)") (class "Default")
      (node (ref "IC5") (pin "5") (pinfunction "RUN_5") (pintype "input"))
      (node (ref "R14") (pin "1") (pinfunction "1_1") (pintype "passive"))
    )
    (net (code "21") (name "Net-(IC5-Rt)") (class "Default")
      (node (ref "IC5") (pin "12") (pinfunction "Rt_12") (pintype "input"))
      (node (ref "R19") (pin "2") (pinfunction "2_2") (pintype "passive"))
    )
    (net (code "22") (name "Net-(IC12-EN)") (class "Default")
      (node (ref "C57") (pin "2") (pinfunction "2_2") (pintype "passive"))
      (node (ref "C58") (pin "2") (pinfunction "2_2") (pintype "passive"))
      (node (ref "IC12") (pin "2") (pinfunction "VIN_2") (pintype "input"))
      (node (ref "IC12") (pin "3") (pinfunction "EN_3") (pintype "input"))
      (node (ref "L1") (pin "2") (pinfunction "2_2") (pintype "passive"))
    )
    (net (code "23") (name "Net-(IC12-FB)") (class "Default")
      (node (ref "IC12") (pin "5") (pinfunction "FB_5") (pintype "input"))
      (node (ref "R81") (pin "1") (pinfunction "1_1") (pintype "passive"))
      (node (ref "R82") (pin "2") (pinfunction "2_2") (pintype "passive"))
    )
    (net (code "24") (name "Net-(IC12-SW)") (class "Default")
      (node (ref "IC12") (pin "9") (pinfunction "SW_9") (pintype "output"))
      (node (ref "L2") (pin "1") (pinfunction "1_1") (pintype "passive"))
    )
    (net (code "25") (name "Net-(IC16A-IN+)") (class "Default")
      (node (ref "IC16") (pin "5") (pinfunction "IN+_5") (pintype "input"))
      (node (ref "R94") (pin "2") (pinfunction "2_2") (pintype "passive"))
      (node (ref "R95") (pin "1") (pinfunction "1_1") (pintype "passive"))
    )
    (net (code "26") (name "Net-(IC16B-IN+)") (class "Default")
      (node (ref "IC16") (pin "7") (pinfunction "IN+_7") (pintype "input"))
      (node (ref "R96") (pin "1") (pinfunction "1_1") (pintype "passive"))
      (node (ref "R97") (pin "2") (pinfunction "2_2") (pintype "passive"))
    )
    (net (code "27") (name "Net-(IC16C-IN+)") (class "Default")
      (node (ref "IC16") (pin "9") (pinfunction "IN+_9") (pintype "input"))
      (node (ref "R98") (pin "1") (pinfunction "1_1") (pintype "passive"))
      (node (ref "R99") (pin "2") (pinfunction "2_2") (pintype "passive"))
    )
    (net (code "28") (name "Net-(IC16D-IN-)") (class "Default")
      (node (ref "IC16") (pin "10") (pinfunction "IN-_10") (pintype "input"))
      (node (ref "R91") (pin "1") (pinfunction "1_1") (pintype "passive"))
      (node (ref "R93") (pin "1") (pinfunction "1_1") (pintype "passive"))
    )
    (net (code "29") (name "Net-(IC19-EN)") (class "Default")
      (node (ref "IC19") (pin "3") (pinfunction "EN_3") (pintype "input"))
      (node (ref "R28") (pin "1") (pinfunction "1_1") (pintype "passive"))
    )
    (net (code "30") (name "Net-(IC19-FB)") (class "Default")
      (node (ref "C71") (pin "1") (pinfunction "1_1") (pintype "passive"))
      (node (ref "C72") (pin "1") (pinfunction "1_1") (pintype "passive"))
      (node (ref "IC19") (pin "6") (pinfunction "FB_6") (pintype "input"))
      (node (ref "R30") (pin "1") (pinfunction "1_1") (pintype "passive"))
      (node (ref "R31") (pin "2") (pinfunction "2_2") (pintype "passive"))
    )
    (net (code "31") (name "Net-(IC19-RON)") (class "Default")
      (node (ref "IC19") (pin "2") (pinfunction "RON_2") (pintype "input"))
      (node (ref "R27") (pin "1") (pinfunction "1_1") (pintype "passive"))
    )
    (net (code "32") (name "Net-(IC19-SS)") (class "Default")
      (node (ref "C70") (pin "2") (pinfunction "2_2") (pintype "passive"))
      (node (ref "IC19") (pin "5") (pinfunction "SS_5") (pintype "passive"))
    )
    (net (code "33") (name "Net-(LD3-A)") (class "Default")
      (node (ref "LD3") (pin "2") (pinfunction "A_2") (pintype "passive"))
      (node (ref "R21") (pin "2") (pinfunction "2_2") (pintype "passive"))
    )
    (net (code "34") (name "Net-(LD16-A)") (class "Default")
      (node (ref "LD16") (pin "2") (pinfunction "A_2") (pintype "passive"))
      (node (ref "R109") (pin "2") (pinfunction "2_2") (pintype "passive"))
    )
    (net (code "35") (name "Net-(LD17-A)") (class "Default")
      (node (ref "LD17") (pin "2") (pinfunction "A_2") (pintype "passive"))
      (node (ref "R110") (pin "1") (pinfunction "1_1") (pintype "passive"))
    )
    (net (code "36") (name "Net-(LD18-C)") (class "Default")
      (node (ref "LD18") (pin "1") (pinfunction "C_1") (pintype "passive"))
      (node (ref "R108") (pin "2") (pinfunction "2_2") (pintype "passive"))
    )
    (net (code "37") (name "Net-(LD19-A)") (class "Default")
      (node (ref "LD19") (pin "2") (pinfunction "A_2") (pintype "passive"))
      (node (ref "R111") (pin "1") (pinfunction "1_1") (pintype "passive"))
    )
    (net (code "38") (name "Net-(R26-Pad1)") (class "Default")
      (node (ref "R26") (pin "1") (pinfunction "1_1") (pintype "passive"))
      (node (ref "R27") (pin "2") (pinfunction "2_2") (pintype "passive"))
    )
    (net (code "39") (name "P3V3") (class "Default")
      (node (ref "C55") (pin "2") (pinfunction "2_2") (pintype "passive"))
      (node (ref "C56") (pin "2") (pinfunction "2_2") (pintype "passive"))
      (node (ref "IC12") (pin "10") (pinfunction "VOS_10") (pintype "input"))
      (node (ref "IC12") (pin "8") (pinfunction "SLEEP_8") (pintype "input"))
      (node (ref "IC16") (pin "3") (pinfunction "V+_3") (pintype "power_in"))
      (node (ref "L2") (pin "2") (pinfunction "2_2") (pintype "passive"))
      (node (ref "R100") (pin "2") (pinfunction "2_2") (pintype "passive"))
      (node (ref "R111") (pin "2") (pinfunction "2_2") (pintype "passive"))
      (node (ref "R14") (pin "2") (pinfunction "2_2") (pintype "passive"))
      (node (ref "R25") (pin "1") (pinfunction "1_1") (pintype "passive"))
      (node (ref "R81") (pin "2") (pinfunction "2_2") (pintype "passive"))
      (node (ref "R92") (pin "1") (pinfunction "1_1") (pintype "passive"))
      (node (ref "R94") (pin "1") (pinfunction "1_1") (pintype "passive"))
    )
    (net (code "40") (name "P5V0") (class "Default")
      (node (ref "C22") (pin "2") (pinfunction "2_2") (pintype "passive"))
      (node (ref "IC4") (pin "1") (pinfunction "VOUT_1") (pintype "power_in"))
      (node (ref "IC4") (pin "2") (pinfunction "SENS_2") (pintype "input"))
      (node (ref "R21") (pin "1") (pinfunction "1_1") (pintype "passive"))
    )
    (net (code "41") (name "P6V5") (class "Default")
      (node (ref "C68") (pin "2") (pinfunction "2_2") (pintype "passive"))
      (node (ref "C69") (pin "2") (pinfunction "2_2") (pintype "passive"))
      (node (ref "C71") (pin "2") (pinfunction "2_2") (pintype "passive"))
      (node (ref "C72") (pin "2") (pinfunction "2_2") (pintype "passive"))
      (node (ref "D3") (pin "2") (pinfunction "A_2") (pintype "passive"))
      (node (ref "IC19") (pin "7") (pinfunction "VOUT_7") (pintype "power_in"))
      (node (ref "R109") (pin "1") (pinfunction "1_1") (pintype "passive"))
      (node (ref "R30") (pin "2") (pinfunction "2_2") (pintype "passive"))
      (node (ref "R98") (pin "2") (pinfunction "2_2") (pintype "passive"))
    )
    (net (code "42") (name "P12V0") (class "Default")
      (node (ref "C24") (pin "2") (pinfunction "2_2") (pintype "passive"))
      (node (ref "C25") (pin "2") (pinfunction "2_2") (pintype "passive"))
      (node (ref "C59") (pin "1") (pinfunction "1_1") (pintype "passive"))
      (node (ref "C64") (pin "2") (pinfunction "2_2") (pintype "passive"))
      (node (ref "C66") (pin "2") (pinfunction "2_2") (pintype "passive"))
      (node (ref "FL2") (pin "2") (pinfunction "CB_2") (pintype "passive"))
      (node (ref "IC19") (pin "1") (pinfunction "VIN_1") (pintype "input"))
      (node (ref "IC5") (pin "3") (pinfunction "Vin_3") (pintype "power_in"))
      (node (ref "IC5") (pin "4") (pinfunction "Vin_4") (pintype "power_in"))
      (node (ref "R26") (pin "2") (pinfunction "2_2") (pintype "passive"))
      (node (ref "R28") (pin "2") (pinfunction "2_2") (pintype "passive"))
    )
    (net (code "43") (name "P30V0") (class "Default")
      (node (ref "C63") (pin "2") (pinfunction "2_2") (pintype "passive"))
      (node (ref "FL1") (pin "2") (pinfunction "CB_2") (pintype "passive"))
      (node (ref "R110") (pin "2") (pinfunction "2_2") (pintype "passive"))
      (node (ref "R96") (pin "2") (pinfunction "2_2") (pintype "passive"))
    )
    (net (code "44") (name "unconnected-(IC4-NC-Pad4)") (class "Default")
      (node (ref "IC4") (pin "4") (pinfunction "NC_4") (pintype "passive"))
    )
    (net (code "45") (name "unconnected-(IC4-PG-Pad7)") (class "Default")
      (node (ref "IC4") (pin "7") (pinfunction "PG_7") (pintype "output"))
    )
    (net (code "46") (name "unconnected-(IC12-NC-Pad4)") (class "Default")
      (node (ref "IC12") (pin "4") (pinfunction "NC_4") (pintype "passive"))
    )
    (net (code "47") (name "unconnected-(IC12-PG-Pad7)") (class "Default")
      (node (ref "IC12") (pin "7") (pinfunction "PG_7") (pintype "output"))
    )
  )
)
